# SheetArduinoNPN.net
KiCad netlist of a schematic drawn in Altium Designer
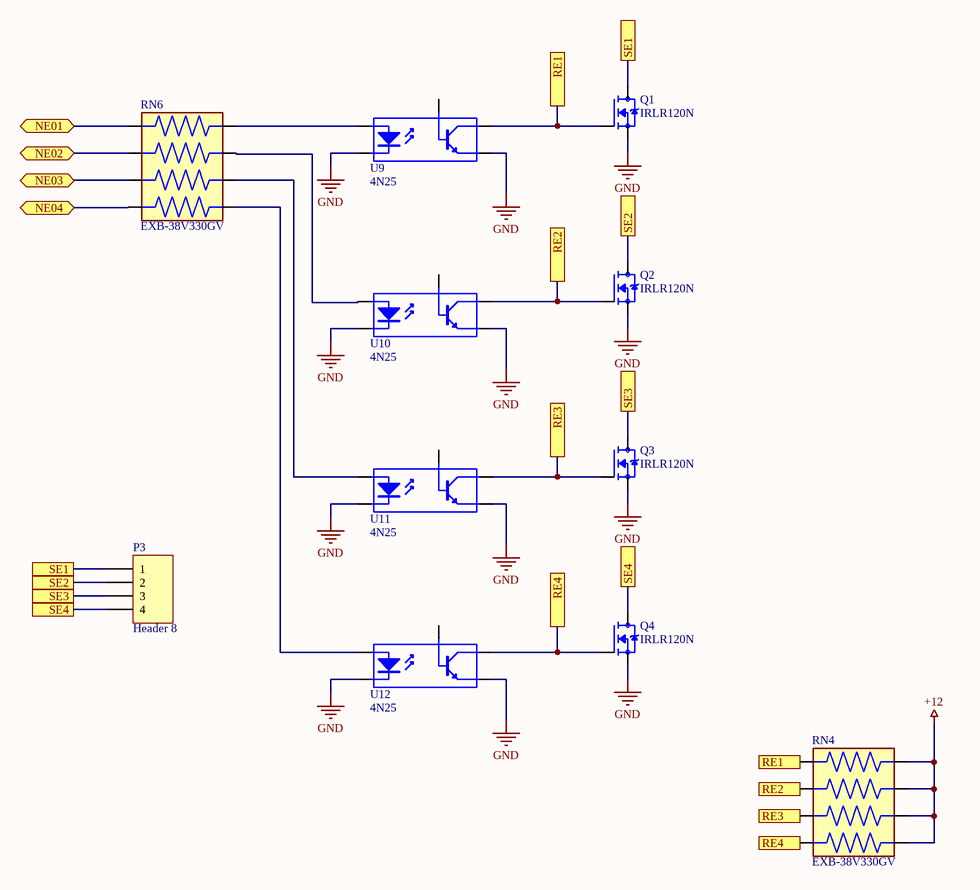
[diagram p0: SheetArduinoNPN.SchDoc]

(export (version "E")
  (design (tool "Eeschema 10.0.6"))
  (components
    (comp (ref "P3")
      (value "Header 8")
      (footprint "HDR1X4")
      (description "Header, 4-Pin")
      (fields (field (name "PUBLISHER") "Altium Limited"))
      (libsource (lib "Miscellaneous Connectors") (part "Header 4"))
    )
    (comp (ref "Q1")
      (value "IRLR120N")
      (footprint "DPAK229P990X239-3N")
      (description "N-Channel 100V 10A _Tc_ 48W _Tc_ Surface Mount D-Pak")
      (fields (field (name "MF") "Infineon Technologies"))
      (libsource (lib "IRLR120N") (part "IRLR120N"))
    )
    (comp (ref "Q2")
      (value "IRLR120N")
      (footprint "DPAK229P990X239-3N")
      (description "N-Channel 100V 10A _Tc_ 48W _Tc_ Surface Mount D-Pak")
      (fields (field (name "MF") "Infineon Technologies"))
      (libsource (lib "IRLR120N") (part "IRLR120N"))
    )
    (comp (ref "Q3")
      (value "IRLR120N")
      (footprint "DPAK229P990X239-3N")
      (description "N-Channel 100V 10A _Tc_ 48W _Tc_ Surface Mount D-Pak")
      (fields (field (name "MF") "Infineon Technologies"))
      (libsource (lib "") (part "IRLR120N_1"))
    )
    (comp (ref "Q4")
      (value "IRLR120N")
      (footprint "DPAK229P990X239-3N")
      (description "N-Channel 100V 10A _Tc_ 48W _Tc_ Surface Mount D-Pak")
      (fields (field (name "MF") "Infineon Technologies"))
      (libsource (lib "IRLR120N") (part "IRLR120N"))
    )
    (comp (ref "RN4")
      (value "EXB-38V330GV")
      (footprint "RESCAXS80P320X160X60-8N")
      (description "Resistor Array, Chip, 4 elements CONVEX 1206 2%")
      (fields (field (name "MF") "Panasonic"))
      (libsource (lib "EXB-38V330GV") (part "EXB-38V330GV"))
    )
    (comp (ref "RN6")
      (value "EXB-38V330GV")
      (footprint "RESCAXS80P320X160X60-8N")
      (description "Resistor Array, Chip, 4 elements CONVEX 1206 2%")
      (fields (field (name "MF") "Panasonic"))
      (libsource (lib "EXB-38V330GV") (part "EXB-38V330GV"))
    )
    (comp (ref "U9")
      (value "4N25")
      (footprint "SOP5(6)")
      (description "5 Pin Mini Flat Pack Optocoupler")
      (fields (field (name "PUBLISHER") "Altium Limited"))
      (libsource (lib "Miscellaneous Devices") (part "Optoisolator2"))
    )
    (comp (ref "U10")
      (value "4N25")
      (footprint "SOP5(6)")
      (description "5 Pin Mini Flat Pack Optocoupler")
      (fields (field (name "PUBLISHER") "Altium Limited"))
      (libsource (lib "Miscellaneous Devices") (part "Optoisolator2"))
    )
    (comp (ref "U11")
      (value "4N25")
      (footprint "SOP5(6)")
      (description "5 Pin Mini Flat Pack Optocoupler")
      (fields (field (name "PUBLISHER") "Altium Limited"))
      (libsource (lib "Miscellaneous Devices") (part "Optoisolator2"))
    )
    (comp (ref "U12")
      (value "4N25")
      (footprint "SOP5(6)")
      (description "5 Pin Mini Flat Pack Optocoupler")
      (fields (field (name "PUBLISHER") "Altium Limited"))
      (libsource (lib "Miscellaneous Devices") (part "Optoisolator2"))
    )
  )
  (nets
    (net (code "1") (name "+12") (class "Default")
      (node (ref "RN4") (pin "5") (pinfunction "5_5") (pintype "passive"))
      (node (ref "RN4") (pin "6") (pinfunction "6_6") (pintype "passive"))
      (node (ref "RN4") (pin "7") (pinfunction "7_7") (pintype "passive"))
      (node (ref "RN4") (pin "8") (pinfunction "8_8") (pintype "passive"))
    )
    (net (code "2") (name "/NE01") (class "Default")
      (node (ref "RN6") (pin "1") (pinfunction "1_1") (pintype "passive"))
    )
    (net (code "3") (name "/NE02") (class "Default")
      (node (ref "RN6") (pin "2") (pinfunction "2_2") (pintype "passive"))
    )
    (net (code "4") (name "/NE03") (class "Default")
      (node (ref "RN6") (pin "3") (pinfunction "3_3") (pintype "passive"))
    )
    (net (code "5") (name "/NE04") (class "Default")
      (node (ref "RN6") (pin "4") (pinfunction "4_4") (pintype "passive"))
    )
    (net (code "6") (name "/RE1") (class "Default")
      (node (ref "Q1") (pin "1") (pinfunction "G_1") (pintype "passive"))
      (node (ref "RN4") (pin "1") (pinfunction "1_1") (pintype "passive"))
      (node (ref "U9") (pin "5") (pinfunction "C_5") (pintype "passive"))
    )
    (net (code "7") (name "/RE2") (class "Default")
      (node (ref "Q2") (pin "1") (pinfunction "G_1") (pintype "passive"))
      (node (ref "RN4") (pin "2") (pinfunction "2_2") (pintype "passive"))
      (node (ref "U10") (pin "5") (pinfunction "C_5") (pintype "passive"))
    )
    (net (code "8") (name "/RE3") (class "Default")
      (node (ref "Q3") (pin "3") (pinfunction "D_3") (pintype "passive"))
      (node (ref "RN4") (pin "3") (pinfunction "3_3") (pintype "passive"))
      (node (ref "U11") (pin "5") (pinfunction "C_5") (pintype "passive"))
    )
    (net (code "9") (name "/RE4") (class "Default")
      (node (ref "Q4") (pin "1") (pinfunction "G_1") (pintype "passive"))
      (node (ref "RN4") (pin "4") (pinfunction "4_4") (pintype "passive"))
      (node (ref "U12") (pin "5") (pinfunction "C_5") (pintype "passive"))
    )
    (net (code "10") (name "/SE1") (class "Default")
      (node (ref "P3") (pin "1") (pinfunction "1_1") (pintype "passive"))
      (node (ref "Q1") (pin "3") (pinfunction "D_3") (pintype "passive"))
    )
    (net (code "11") (name "/SE2") (class "Default")
      (node (ref "P3") (pin "2") (pinfunction "2_2") (pintype "passive"))
      (node (ref "Q2") (pin "3") (pinfunction "D_3") (pintype "passive"))
    )
    (net (code "12") (name "/SE3") (class "Default")
      (node (ref "P3") (pin "3") (pinfunction "3_3") (pintype "passive"))
      (node (ref "Q3") (pin "3") (pinfunction "D_3") (pintype "passive"))
    )
    (net (code "13") (name "/SE4") (class "Default")
      (node (ref "P3") (pin "4") (pinfunction "4_4") (pintype "passive"))
      (node (ref "Q4") (pin "3") (pinfunction "D_3") (pintype "passive"))
    )
    (net (code "14") (name "GND") (class "Default")
      (node (ref "Q1") (pin "2") (pinfunction "S_2") (pintype "passive"))
      (node (ref "Q2") (pin "2") (pinfunction "S_2") (pintype "passive"))
      (node (ref "Q3") (pin "2") (pinfunction "S_2") (pintype "passive"))
      (node (ref "Q4") (pin "2") (pinfunction "S_2") (pintype "passive"))
      (node (ref "U10") (pin "3") (pinfunction "K_3") (pintype "passive"))
      (node (ref "U10") (pin "4") (pinfunction "E_4") (pintype "passive"))
      (node (ref "U11") (pin "3") (pinfunction "K_3") (pintype "passive"))
      (node (ref "U11") (pin "4") (pinfunction "E_4") (pintype "passive"))
      (node (ref "U12") (pin "3") (pinfunction "K_3") (pintype "passive"))
      (node (ref "U12") (pin "4") (pinfunction "E_4") (pintype "passive"))
      (node (ref "U9") (pin "3") (pinfunction "K_3") (pintype "passive"))
      (node (ref "U9") (pin "4") (pinfunction "E_4") (pintype "passive"))
    )
    (net (code "15") (name "Net-(U9-A)") (class "Default")
      (node (ref "RN6") (pin "8") (pinfunction "8_8") (pintype "passive"))
      (node (ref "U9") (pin "1") (pinfunction "A_1") (pintype "passive"))
    )
    (net (code "16") (name "Net-(U10-A)") (class "Default")
      (node (ref "RN6") (pin "7") (pinfunction "7_7") (pintype "passive"))
      (node (ref "U10") (pin "1") (pinfunction "A_1") (pintype "passive"))
    )
    (net (code "17") (name "Net-(U11-A)") (class "Default")
      (node (ref "RN6") (pin "6") (pinfunction "6_6") (pintype "passive"))
      (node (ref "U11") (pin "1") (pinfunction "A_1") (pintype "passive"))
    )
    (net (code "18") (name "Net-(U12-A)") (class "Default")
      (node (ref "RN6") (pin "5") (pinfunction "5_5") (pintype "passive"))
      (node (ref "U12") (pin "1") (pinfunction "A_1") (pintype "passive"))
    )
    (net (code "19") (name "unconnected-(U9-B-Pad6)") (class "Default")
      (node (ref "U9") (pin "6") (pinfunction "B_6") (pintype "passive"))
    )
    (net (code "20") (name "unconnected-(U10-B-Pad6)") (class "Default")
      (node (ref "U10") (pin "6") (pinfunction "B_6") (pintype "passive"))
    )
    (net (code "21") (name "unconnected-(U11-B-Pad6)") (class "Default")
      (node (ref "U11") (pin "6") (pinfunction "B_6") (pintype "passive"))
    )
    (net (code "22") (name "unconnected-(U12-B-Pad6)") (class "Default")
      (node (ref "U12") (pin "6") (pinfunction "B_6") (pintype "passive"))
    )
  )
)
